# Small_e-PaperShield_v2_1.net
KiCad netlist of a schematic drawn in EAGLE
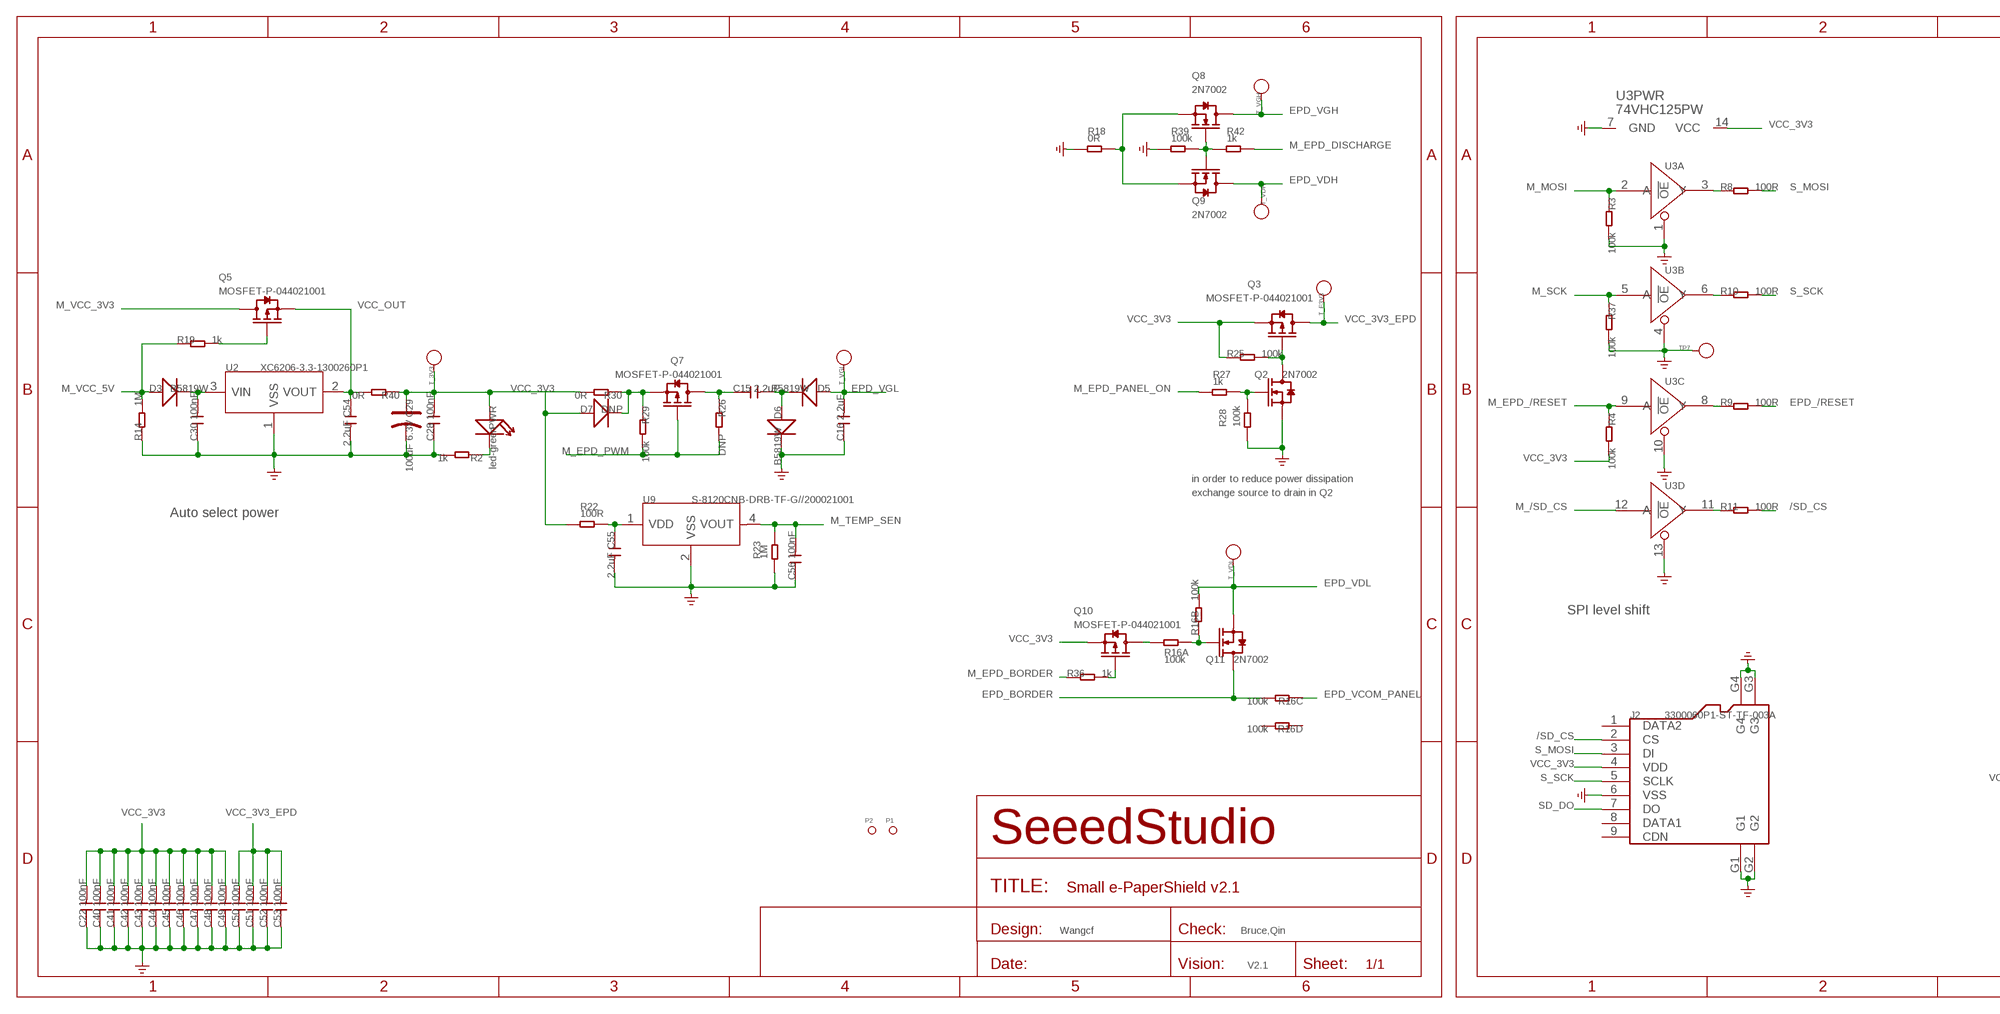
[diagram p0: schematic, sheet 1, part 1 of 2]
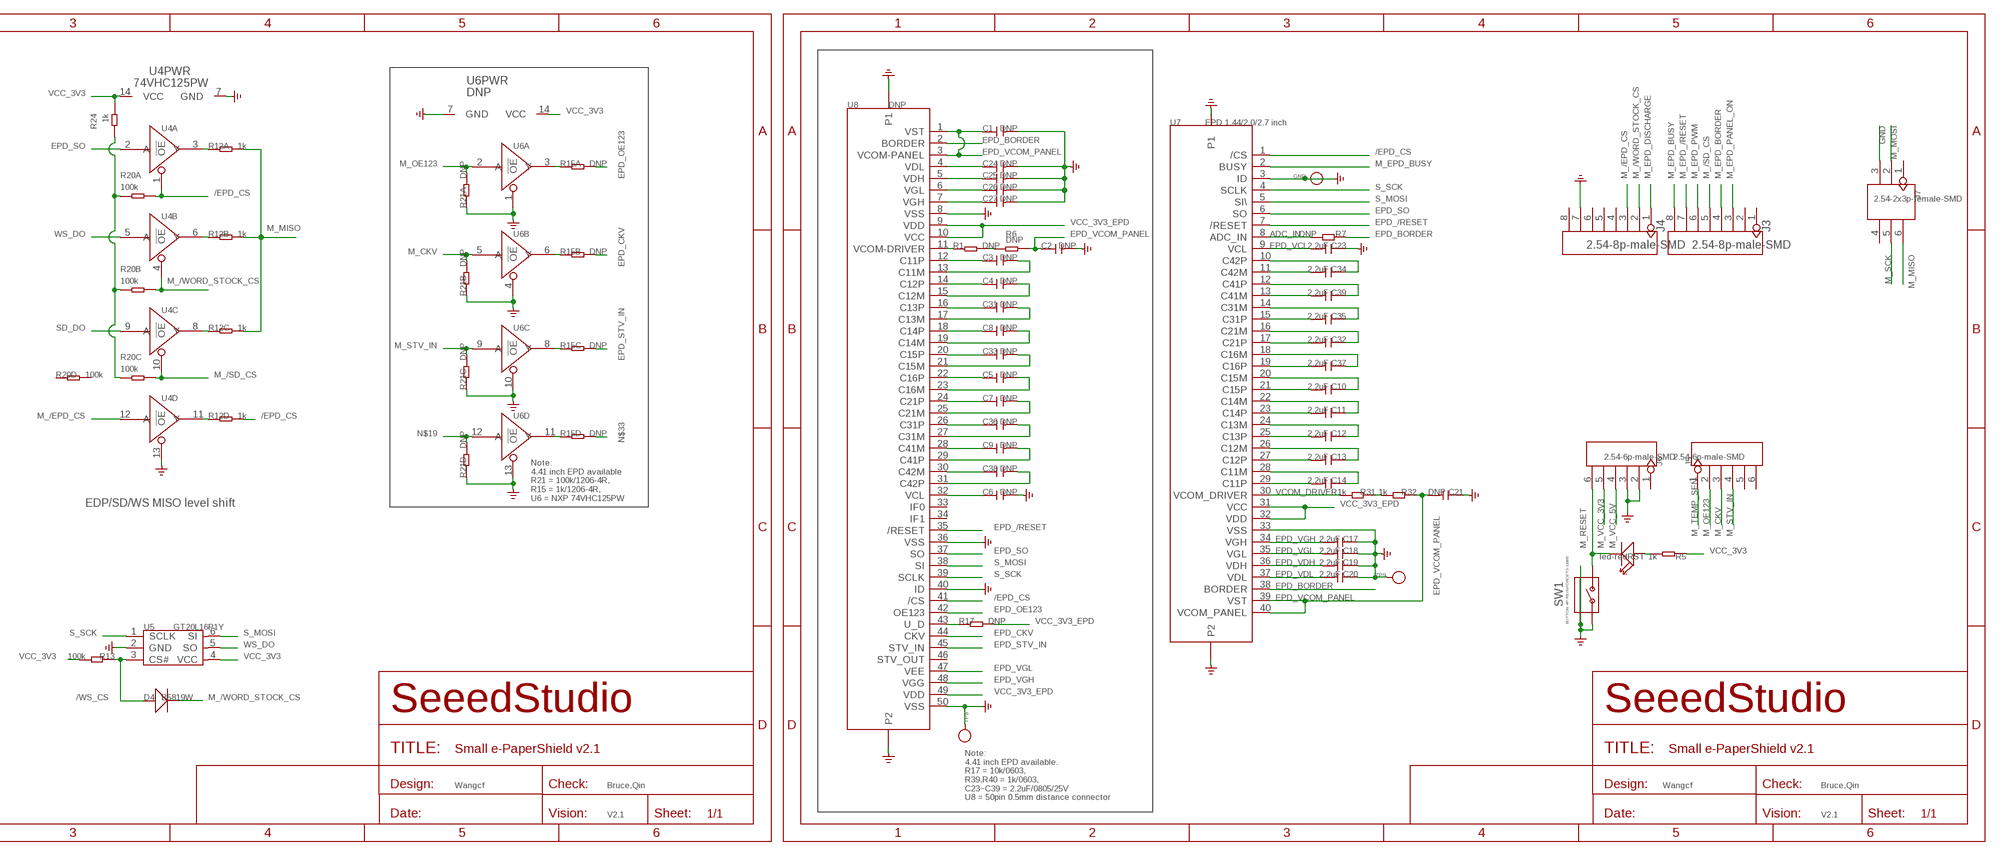
[diagram p1: schematic, sheet 1, part 2 of 2]

(export (version "E")
  (design (tool "Eeschema 10.0.6"))
  (components
    (comp (ref "C1")
      (value "DNP")
      (footprint "eagle-import:C0805")
      (libsource (lib "eagle-import") (part "C-0805"))
    )
    (comp (ref "C2")
      (value "DNP")
      (footprint "eagle-import:C0805")
      (libsource (lib "eagle-import") (part "C-0805"))
    )
    (comp (ref "C3")
      (value "DNP")
      (footprint "eagle-import:C0805")
      (libsource (lib "eagle-import") (part "C-0805"))
    )
    (comp (ref "C4")
      (value "DNP")
      (footprint "eagle-import:C0805")
      (libsource (lib "eagle-import") (part "C-0805"))
    )
    (comp (ref "C5")
      (value "DNP")
      (footprint "eagle-import:C0805")
      (libsource (lib "eagle-import") (part "C-0805"))
    )
    (comp (ref "C6")
      (value "DNP")
      (footprint "eagle-import:C0805")
      (libsource (lib "eagle-import") (part "C-0805"))
    )
    (comp (ref "C7")
      (value "DNP")
      (footprint "eagle-import:C0805")
      (libsource (lib "eagle-import") (part "C-0805"))
    )
    (comp (ref "C8")
      (value "DNP")
      (footprint "eagle-import:C0805")
      (libsource (lib "eagle-import") (part "C-0805"))
    )
    (comp (ref "C9")
      (value "DNP")
      (footprint "eagle-import:C0805")
      (libsource (lib "eagle-import") (part "C-0805"))
    )
    (comp (ref "C10")
      (value "2.2uF")
      (footprint "eagle-import:C0805")
      (libsource (lib "eagle-import") (part "C-0805"))
    )
    (comp (ref "C11")
      (value "2.2uF")
      (footprint "eagle-import:C0805")
      (libsource (lib "eagle-import") (part "C-0805"))
    )
    (comp (ref "C12")
      (value "2.2uF")
      (footprint "eagle-import:C0805")
      (libsource (lib "eagle-import") (part "C-0805"))
    )
    (comp (ref "C13")
      (value "2.2uF")
      (footprint "eagle-import:C0805")
      (libsource (lib "eagle-import") (part "C-0805"))
    )
    (comp (ref "C14")
      (value "2.2uF")
      (footprint "eagle-import:C0805")
      (libsource (lib "eagle-import") (part "C-0805"))
    )
    (comp (ref "C15")
      (value "2.2uF")
      (footprint "eagle-import:C0805")
      (libsource (lib "eagle-import") (part "C-0805"))
    )
    (comp (ref "C16")
      (value "2.2uF")
      (footprint "eagle-import:C0805")
      (libsource (lib "eagle-import") (part "C-0805"))
    )
    (comp (ref "C17")
      (value "2.2uF")
      (footprint "eagle-import:C0805")
      (libsource (lib "eagle-import") (part "C-0805"))
    )
    (comp (ref "C18")
      (value "2.2uF")
      (footprint "eagle-import:C0805")
      (libsource (lib "eagle-import") (part "C-0805"))
    )
    (comp (ref "C19")
      (value "2.2uF")
      (footprint "eagle-import:C0805")
      (libsource (lib "eagle-import") (part "C-0805"))
    )
    (comp (ref "C20")
      (value "2.2uF")
      (footprint "eagle-import:C0805")
      (libsource (lib "eagle-import") (part "C-0805"))
    )
    (comp (ref "C21")
      (value "DNP")
      (footprint "eagle-import:C0805")
      (libsource (lib "eagle-import") (part "C-0805"))
    )
    (comp (ref "C22")
      (value "100nF")
      (footprint "eagle-import:C0603")
      (libsource (lib "eagle-import") (part "C-0603"))
    )
    (comp (ref "C23")
      (value "2.2uF")
      (footprint "eagle-import:C0805")
      (libsource (lib "eagle-import") (part "C-0805"))
    )
    (comp (ref "C24")
      (value "DNP")
      (footprint "eagle-import:C0805")
      (libsource (lib "eagle-import") (part "C-0805"))
    )
    (comp (ref "C25")
      (value "DNP")
      (footprint "eagle-import:C0805")
      (libsource (lib "eagle-import") (part "C-0805"))
    )
    (comp (ref "C26")
      (value "DNP")
      (footprint "eagle-import:C0805")
      (libsource (lib "eagle-import") (part "C-0805"))
    )
    (comp (ref "C27")
      (value "DNP")
      (footprint "eagle-import:C0805")
      (libsource (lib "eagle-import") (part "C-0805"))
    )
    (comp (ref "C28")
      (value "100nF")
      (footprint "eagle-import:C0603")
      (libsource (lib "eagle-import") (part "C-0603"))
    )
    (comp (ref "C29")
      (value "100uF 6.3V")
      (footprint "eagle-import:AVX-B")
      (libsource (lib "eagle-import") (part "CAP-AVX-B"))
    )
    (comp (ref "C30")
      (value "100nF")
      (footprint "eagle-import:C0603")
      (libsource (lib "eagle-import") (part "C-0603"))
    )
    (comp (ref "C31")
      (value "DNP")
      (footprint "eagle-import:C0805")
      (libsource (lib "eagle-import") (part "C-0805"))
    )
    (comp (ref "C32")
      (value "2.2uF")
      (footprint "eagle-import:C0805")
      (libsource (lib "eagle-import") (part "C-0805"))
    )
    (comp (ref "C33")
      (value "DNP")
      (footprint "eagle-import:C0805")
      (libsource (lib "eagle-import") (part "C-0805"))
    )
    (comp (ref "C34")
      (value "2.2uF")
      (footprint "eagle-import:C0805")
      (libsource (lib "eagle-import") (part "C-0805"))
    )
    (comp (ref "C35")
      (value "2.2uF")
      (footprint "eagle-import:C0805")
      (libsource (lib "eagle-import") (part "C-0805"))
    )
    (comp (ref "C36")
      (value "DNP")
      (footprint "eagle-import:C0805")
      (libsource (lib "eagle-import") (part "C-0805"))
    )
    (comp (ref "C37")
      (value "2.2uF")
      (footprint "eagle-import:C0805")
      (libsource (lib "eagle-import") (part "C-0805"))
    )
    (comp (ref "C38")
      (value "DNP")
      (footprint "eagle-import:C0805")
      (libsource (lib "eagle-import") (part "C-0805"))
    )
    (comp (ref "C39")
      (value "2.2uF")
      (footprint "eagle-import:C0805")
      (libsource (lib "eagle-import") (part "C-0805"))
    )
    (comp (ref "C40")
      (value "100nF")
      (footprint "eagle-import:C0603")
      (libsource (lib "eagle-import") (part "C-0603"))
    )
    (comp (ref "C41")
      (value "100nF")
      (footprint "eagle-import:C0603")
      (libsource (lib "eagle-import") (part "C-0603"))
    )
    (comp (ref "C42")
      (value "100nF")
      (footprint "eagle-import:C0603")
      (libsource (lib "eagle-import") (part "C-0603"))
    )
    (comp (ref "C43")
      (value "100nF")
      (footprint "eagle-import:C0603")
      (libsource (lib "eagle-import") (part "C-0603"))
    )
    (comp (ref "C44")
      (value "100nF")
      (footprint "eagle-import:C0603")
      (libsource (lib "eagle-import") (part "C-0603"))
    )
    (comp (ref "C45")
      (value "100nF")
      (footprint "eagle-import:C0603")
      (libsource (lib "eagle-import") (part "C-0603"))
    )
    (comp (ref "C46")
      (value "100nF")
      (footprint "eagle-import:C0603")
      (libsource (lib "eagle-import") (part "C-0603"))
    )
    (comp (ref "C47")
      (value "100nF")
      (footprint "eagle-import:C0603")
      (libsource (lib "eagle-import") (part "C-0603"))
    )
    (comp (ref "C48")
      (value "100nF")
      (footprint "eagle-import:C0603")
      (libsource (lib "eagle-import") (part "C-0603"))
    )
    (comp (ref "C49")
      (value "100nF")
      (footprint "eagle-import:C0603")
      (libsource (lib "eagle-import") (part "C-0603"))
    )
    (comp (ref "C50")
      (value "100nF")
      (footprint "eagle-import:C0603")
      (libsource (lib "eagle-import") (part "C-0603"))
    )
    (comp (ref "C51")
      (value "100nF")
      (footprint "eagle-import:C0603")
      (libsource (lib "eagle-import") (part "C-0603"))
    )
    (comp (ref "C52")
      (value "100nF")
      (footprint "eagle-import:C0603")
      (libsource (lib "eagle-import") (part "C-0603"))
    )
    (comp (ref "C53")
      (value "100nF")
      (footprint "eagle-import:C0603")
      (libsource (lib "eagle-import") (part "C-0603"))
    )
    (comp (ref "C54")
      (value "2.2uF")
      (footprint "eagle-import:C0805")
      (libsource (lib "eagle-import") (part "C-0805"))
    )
    (comp (ref "C55")
      (value "2.2uF")
      (footprint "eagle-import:C0805")
      (libsource (lib "eagle-import") (part "C-0805"))
    )
    (comp (ref "C56")
      (value "100nF")
      (footprint "eagle-import:C0603")
      (libsource (lib "eagle-import") (part "C-0603"))
    )
    (comp (ref "D3")
      (value "B5819W")
      (footprint "eagle-import:SOD123")
      (libsource (lib "eagle-import") (part "D'1206'"))
    )
    (comp (ref "D4")
      (value "B5819W")
      (footprint "eagle-import:SOD123")
      (libsource (lib "eagle-import") (part "D'1206'"))
    )
    (comp (ref "D5")
      (value "B5819W")
      (footprint "eagle-import:SOD123")
      (libsource (lib "eagle-import") (part "D'1206'"))
    )
    (comp (ref "D6")
      (value "B5819W")
      (footprint "eagle-import:SOD123")
      (libsource (lib "eagle-import") (part "D'1206'"))
    )
    (comp (ref "D7")
      (value "DNP")
      (footprint "eagle-import:SOD123")
      (libsource (lib "eagle-import") (part "D'1206'"))
    )
    (comp (ref "GND")
      (value "PAD-TEST-POINT'3535'")
      (footprint "eagle-import:TP_3535")
      (fields (field (name "PARTNO") "DNP"))
      (libsource (lib "eagle-import") (part "PAD-TEST-POINT'3535'"))
    )
    (comp (ref "J2")
      (value "3300060P1-ST-TF-003A")
      (footprint "eagle-import:9P-SMD-W_-RING")
      (libsource (lib "eagle-import") (part "3300060P1-ST-TF-003A"))
    )
    (comp (ref "J3")
      (value "2.54-8p-male-SMD")
      (footprint "eagle-import:8P-2.54-SMD")
      (libsource (lib "eagle-import") (part "HEADER-8P-2.54-SMD"))
    )
    (comp (ref "J4")
      (value "2.54-8p-male-SMD")
      (footprint "eagle-import:8P-2.54-SMD")
      (libsource (lib "eagle-import") (part "HEADER-8P-2.54-SMD"))
    )
    (comp (ref "J5")
      (value "2.54-6p-male-SMD")
      (footprint "eagle-import:6P-2.54-SMD")
      (libsource (lib "eagle-import") (part "HEADER-6P-SMD"))
    )
    (comp (ref "J6")
      (value "2.54-6p-male-SMD")
      (footprint "eagle-import:6P-2.54-SMD")
      (libsource (lib "eagle-import") (part "HEADER-6P-SMD"))
    )
    (comp (ref "J7")
      (value "2.54-2x3p-female-SMD")
      (footprint "eagle-import:2X3P-2.54-SMD")
      (libsource (lib "eagle-import") (part "HEADER-2X3P-SMD"))
    )
    (comp (ref "P1")
      (value "PAD-MARK")
      (footprint "eagle-import:ROUND-MARK-1.0")
      (fields (field (name "PARTNO") "DNP"))
      (libsource (lib "eagle-import") (part "PAD-MARK"))
    )
    (comp (ref "P2")
      (value "PAD-MARK")
      (footprint "eagle-import:ROUND-MARK-1.0")
      (fields (field (name "PARTNO") "DNP"))
      (libsource (lib "eagle-import") (part "PAD-MARK"))
    )
    (comp (ref "PWR")
      (value "led-green")
      (footprint "eagle-import:LED-SIDE-VIEW-0603-RIGHT")
      (libsource (lib "eagle-import") (part "LED'RIGHT'"))
    )
    (comp (ref "Q2")
      (value "2N7002")
      (footprint "eagle-import:SOT23")
      (libsource (lib "eagle-import") (part "MOSFET-N'SOT23'"))
    )
    (comp (ref "Q3")
      (value "MOSFET-P-044021001")
      (footprint "eagle-import:SOT23")
      (libsource (lib "eagle-import") (part "MOSFET-P-044021001"))
    )
    (comp (ref "Q5")
      (value "MOSFET-P-044021001")
      (footprint "eagle-import:SOT23")
      (libsource (lib "eagle-import") (part "MOSFET-P-044021001"))
    )
    (comp (ref "Q7")
      (value "MOSFET-P-044021001")
      (footprint "eagle-import:SOT23")
      (libsource (lib "eagle-import") (part "MOSFET-P-044021001"))
    )
    (comp (ref "Q8")
      (value "2N7002")
      (footprint "eagle-import:SOT23")
      (libsource (lib "eagle-import") (part "MOSFET-N'SOT23'"))
    )
    (comp (ref "Q9")
      (value "2N7002")
      (footprint "eagle-import:SOT23")
      (libsource (lib "eagle-import") (part "MOSFET-N'SOT23'"))
    )
    (comp (ref "Q10")
      (value "MOSFET-P-044021001")
      (footprint "eagle-import:SOT23")
      (libsource (lib "eagle-import") (part "MOSFET-P-044021001"))
    )
    (comp (ref "Q11")
      (value "2N7002")
      (footprint "eagle-import:SOT23")
      (libsource (lib "eagle-import") (part "MOSFET-N'SOT23'"))
    )
    (comp (ref "R1")
      (value "DNP")
      (footprint "eagle-import:R0603")
      (libsource (lib "eagle-import") (part "R-0603"))
    )
    (comp (ref "R2")
      (value "1k")
      (footprint "eagle-import:R0603")
      (libsource (lib "eagle-import") (part "R-0603"))
    )
    (comp (ref "R3")
      (value "100k")
      (footprint "eagle-import:R0603")
      (libsource (lib "eagle-import") (part "R-0603"))
    )
    (comp (ref "R4")
      (value "100k")
      (footprint "eagle-import:R0603")
      (libsource (lib "eagle-import") (part "R-0603"))
    )
    (comp (ref "R5")
      (value "1k")
      (footprint "eagle-import:R0603")
      (libsource (lib "eagle-import") (part "R-0603"))
    )
    (comp (ref "R6")
      (value "DNP")
      (footprint "eagle-import:R0603")
      (libsource (lib "eagle-import") (part "R-0603"))
    )
    (comp (ref "R7")
      (value "DNP")
      (footprint "eagle-import:R0603")
      (libsource (lib "eagle-import") (part "R-0603"))
    )
    (comp (ref "R8")
      (value "100R")
      (footprint "eagle-import:R0603")
      (libsource (lib "eagle-import") (part "R-0603"))
    )
    (comp (ref "R9")
      (value "100R")
      (footprint "eagle-import:R0603")
      (libsource (lib "eagle-import") (part "R-0603"))
    )
    (comp (ref "R10")
      (value "100R")
      (footprint "eagle-import:R0603")
      (libsource (lib "eagle-import") (part "R-0603"))
    )
    (comp (ref "R11")
      (value "100R")
      (footprint "eagle-import:R0603")
      (libsource (lib "eagle-import") (part "R-0603"))
    )
    (comp (ref "R12")
      (value "1k")
      (footprint "eagle-import:1206-8-3.3X2.4")
      (libsource (lib "eagle-import") (part "R-4R-1206"))
    )
    (comp (ref "R13")
      (value "100k")
      (footprint "eagle-import:R0603")
      (libsource (lib "eagle-import") (part "R-0603"))
    )
    (comp (ref "R14")
      (value "1M")
      (footprint "eagle-import:R0603")
      (libsource (lib "eagle-import") (part "R-0603"))
    )
    (comp (ref "R15")
      (value "DNP")
      (footprint "eagle-import:1206-8-3.3X2.4")
      (libsource (lib "eagle-import") (part "R-4R-1206"))
    )
    (comp (ref "R16")
      (value "100k")
      (footprint "eagle-import:1206-8-3.3X2.4")
      (libsource (lib "eagle-import") (part "R-4R-1206"))
    )
    (comp (ref "R17")
      (value "DNP")
      (footprint "eagle-import:R0603")
      (libsource (lib "eagle-import") (part "R-0603"))
    )
    (comp (ref "R18")
      (value "0R")
      (footprint "eagle-import:R0603")
      (libsource (lib "eagle-import") (part "R-0603"))
    )
    (comp (ref "R19")
      (value "1k")
      (footprint "eagle-import:R0603")
      (libsource (lib "eagle-import") (part "R-0603"))
    )
    (comp (ref "R20")
      (value "100k")
      (footprint "eagle-import:1206-8-3.3X2.4")
      (libsource (lib "eagle-import") (part "R-4R-1206"))
    )
    (comp (ref "R21")
      (value "DNP")
      (footprint "eagle-import:1206-8-3.3X2.4")
      (libsource (lib "eagle-import") (part "R-4R-1206"))
    )
    (comp (ref "R22")
      (value "100R")
      (footprint "eagle-import:R0603")
      (libsource (lib "eagle-import") (part "R-0603"))
    )
    (comp (ref "R23")
      (value "1M")
      (footprint "eagle-import:R0603")
      (libsource (lib "eagle-import") (part "R-0603"))
    )
    (comp (ref "R24")
      (value "1k")
      (footprint "eagle-import:R0603")
      (libsource (lib "eagle-import") (part "R-0603"))
    )
    (comp (ref "R25")
      (value "100k")
      (footprint "eagle-import:R0603")
      (libsource (lib "eagle-import") (part "R-0603"))
    )
    (comp (ref "R26")
      (value "DNP")
      (footprint "eagle-import:R0603")
      (libsource (lib "eagle-import") (part "R-0603"))
    )
    (comp (ref "R27")
      (value "1k")
      (footprint "eagle-import:R0603")
      (libsource (lib "eagle-import") (part "R-0603"))
    )
    (comp (ref "R28")
      (value "100k")
      (footprint "eagle-import:R0603")
      (libsource (lib "eagle-import") (part "R-0603"))
    )
    (comp (ref "R29")
      (value "100k")
      (footprint "eagle-import:R0603")
      (libsource (lib "eagle-import") (part "R-0603"))
    )
    (comp (ref "R30")
      (value "0R")
      (footprint "eagle-import:R0603")
      (libsource (lib "eagle-import") (part "R-0603"))
    )
    (comp (ref "R31")
      (value "1k")
      (footprint "eagle-import:R0603")
      (libsource (lib "eagle-import") (part "R-0603"))
    )
    (comp (ref "R32")
      (value "1k")
      (footprint "eagle-import:R0603")
      (libsource (lib "eagle-import") (part "R-0603"))
    )
    (comp (ref "R36")
      (value "1k")
      (footprint "eagle-import:R0603")
      (libsource (lib "eagle-import") (part "R-0603"))
    )
    (comp (ref "R37")
      (value "100k")
      (footprint "eagle-import:R0603")
      (libsource (lib "eagle-import") (part "R-0603"))
    )
    (comp (ref "R39")
      (value "100k")
      (footprint "eagle-import:R0603")
      (libsource (lib "eagle-import") (part "R-0603"))
    )
    (comp (ref "R40")
      (value "0R")
      (footprint "eagle-import:R0603")
      (libsource (lib "eagle-import") (part "R-0603"))
    )
    (comp (ref "R42")
      (value "1k")
      (footprint "eagle-import:R0603")
      (libsource (lib "eagle-import") (part "R-0603"))
    )
    (comp (ref "RST")
      (value "led-red")
      (footprint "eagle-import:LED-SIDE-VIEW-0603-RIGHT")
      (libsource (lib "eagle-import") (part "LED'RIGHT'"))
    )
    (comp (ref "SW1")
      (value "BUTTON-4P-REINFORCE'TS-1188E'")
      (footprint "eagle-import:4P-SMD-7X3.5X3.5H")
      (libsource (lib "eagle-import") (part "BUTTON-4P-REINFORCE'TS-1188E'"))
    )
    (comp (ref "TP7")
      (value "PAD-TEST-POINT'3535'")
      (footprint "eagle-import:TP_3535")
      (fields (field (name "PARTNO") "DNP"))
      (libsource (lib "eagle-import") (part "PAD-TEST-POINT'3535'"))
    )
    (comp (ref "TP8")
      (value "PAD-TEST-POINT'3535'")
      (footprint "eagle-import:TP_3535")
      (fields (field (name "PARTNO") "DNP"))
      (libsource (lib "eagle-import") (part "PAD-TEST-POINT'3535'"))
    )
    (comp (ref "TP9")
      (value "PAD-TEST-POINT'3535'")
      (footprint "eagle-import:TP_3535")
      (fields (field (name "PARTNO") "DNP"))
      (libsource (lib "eagle-import") (part "PAD-TEST-POINT'3535'"))
    )
    (comp (ref "T_3V3")
      (value "PAD-TEST-POINT'3535'")
      (footprint "eagle-import:TP_3535")
      (fields (field (name "PARTNO") "DNP"))
      (libsource (lib "eagle-import") (part "PAD-TEST-POINT'3535'"))
    )
    (comp (ref "T_E3V3")
      (value "PAD-TEST-POINT'3535'")
      (footprint "eagle-import:TP_3535")
      (fields (field (name "PARTNO") "DNP"))
      (libsource (lib "eagle-import") (part "PAD-TEST-POINT'3535'"))
    )
    (comp (ref "T_VDH")
      (value "PAD-TEST-POINT'3535'")
      (footprint "eagle-import:TP_3535")
      (fields (field (name "PARTNO") "DNP"))
      (libsource (lib "eagle-import") (part "PAD-TEST-POINT'3535'"))
    )
    (comp (ref "T_VDL")
      (value "PAD-TEST-POINT'3535'")
      (footprint "eagle-import:TP_3535")
      (fields (field (name "PARTNO") "DNP"))
      (libsource (lib "eagle-import") (part "PAD-TEST-POINT'3535'"))
    )
    (comp (ref "T_VGH")
      (value "PAD-TEST-POINT'3535'")
      (footprint "eagle-import:TP_3535")
      (fields (field (name "PARTNO") "DNP"))
      (libsource (lib "eagle-import") (part "PAD-TEST-POINT'3535'"))
    )
    (comp (ref "T_VGL")
      (value "PAD-TEST-POINT'3535'")
      (footprint "eagle-import:TP_3535")
      (fields (field (name "PARTNO") "DNP"))
      (libsource (lib "eagle-import") (part "PAD-TEST-POINT'3535'"))
    )
    (comp (ref "U2")
      (value "XC6206-3.3-1300260P1")
      (footprint "eagle-import:SOT23")
      (libsource (lib "eagle-import") (part "XC6206-3.3-1300260P1"))
    )
    (comp (ref "U3")
      (value "74VHC125PW")
      (footprint "eagle-import:TSSOP14")
      (libsource (lib "eagle-import") (part "74V125PWHC"))
    )
    (comp (ref "U4")
      (value "74VHC125PW")
      (footprint "eagle-import:TSSOP14")
      (libsource (lib "eagle-import") (part "74V125PWHC"))
    )
    (comp (ref "U5")
      (value "GT20L16P1Y")
      (footprint "eagle-import:SOT23-6")
      (libsource (lib "eagle-import") (part "GT20L16P1Y"))
    )
    (comp (ref "U6")
      (value "DNP")
      (footprint "eagle-import:TSSOP14")
      (libsource (lib "eagle-import") (part "74V125PWHC"))
    )
    (comp (ref "U7")
      (value "EPD 1.44/2.0/2.7 inch")
      (footprint "eagle-import:40P-0.5")
      (libsource (lib "eagle-import") (part "TFT-EPD-PANEL"))
    )
    (comp (ref "U8")
      (value "DNP")
      (footprint "eagle-import:50P-0.5")
      (libsource (lib "eagle-import") (part "template_TFT-EPD-PANEL"))
    )
    (comp (ref "U9")
      (value "S-8120CNB-DRB-TF-G//200021001")
      (footprint "eagle-import:SC-82AB")
      (libsource (lib "eagle-import") (part "S-8110C/8120C"))
    )
  )
  (nets
    (net (code "1") (name "/ADC_IN") (class "Default")
      (node (ref "R7") (pin "2") (pinfunction "2_2") (pintype "passive"))
      (node (ref "U7") (pin "8") (pinfunction "ADC_IN_8") (pintype "bidirectional"))
    )
    (net (code "2") (name "/EPD_BORDER") (class "Default")
      (node (ref "Q11") (pin "3") (pinfunction "D_3") (pintype "passive"))
      (node (ref "R16") (pin "6") (pinfunction "2_6") (pintype "passive"))
      (node (ref "R7") (pin "1") (pinfunction "1_1") (pintype "passive"))
      (node (ref "U7") (pin "38") (pinfunction "BORDER_38") (pintype "bidirectional"))
      (node (ref "U8") (pin "2") (pinfunction "BORDER_2") (pintype "bidirectional"))
    )
    (net (code "3") (name "/EPD_CKV") (class "Default")
      (node (ref "R15") (pin "7") (pinfunction "2_7") (pintype "passive"))
      (node (ref "U8") (pin "44") (pinfunction "CKV_44") (pintype "bidirectional"))
    )
    (net (code "4") (name "/EPD_OE123") (class "Default")
      (node (ref "R15") (pin "8") (pinfunction "2_8") (pintype "passive"))
      (node (ref "U8") (pin "42") (pinfunction "OE123_42") (pintype "bidirectional"))
    )
    (net (code "5") (name "/EPD_SO") (class "Default")
      (node (ref "U4") (pin "2") (pinfunction "A_2") (pintype "bidirectional"))
      (node (ref "U7") (pin "6") (pinfunction "SO_6") (pintype "bidirectional"))
      (node (ref "U8") (pin "37") (pinfunction "SO_37") (pintype "bidirectional"))
    )
    (net (code "6") (name "/EPD_STV_IN") (class "Default")
      (node (ref "R15") (pin "6") (pinfunction "2_6") (pintype "passive"))
      (node (ref "U8") (pin "45") (pinfunction "STV_IN_45") (pintype "bidirectional"))
    )
    (net (code "7") (name "/EPD_VCL") (class "Default")
      (node (ref "C23") (pin "2") (pinfunction "2_2") (pintype "passive"))
      (node (ref "U7") (pin "9") (pinfunction "VCL_9") (pintype "bidirectional"))
    )
    (net (code "8") (name "/EPD_VCOM_PANEL") (class "Default")
      (node (ref "C1") (pin "1") (pinfunction "1_1") (pintype "passive"))
      (node (ref "C2") (pin "1") (pinfunction "1_1") (pintype "passive"))
      (node (ref "C21") (pin "2") (pinfunction "2_2") (pintype "passive"))
      (node (ref "R16") (pin "3") (pinfunction "1_3") (pintype "passive"))
      (node (ref "R32") (pin "1") (pinfunction "1_1") (pintype "passive"))
      (node (ref "R6") (pin "2") (pinfunction "2_2") (pintype "passive"))
      (node (ref "U7") (pin "39") (pinfunction "VST_39") (pintype "bidirectional"))
      (node (ref "U7") (pin "40") (pinfunction "VCOM_PANEL_40") (pintype "bidirectional"))
      (node (ref "U8") (pin "1") (pinfunction "VST_1") (pintype "bidirectional"))
      (node (ref "U8") (pin "3") (pinfunction "VCOM-PANEL_3") (pintype "bidirectional"))
    )
    (net (code "9") (name "/EPD_VDH") (class "Default")
      (node (ref "C19") (pin "2") (pinfunction "2_2") (pintype "passive"))
      (node (ref "C25") (pin "1") (pinfunction "1_1") (pintype "passive"))
      (node (ref "Q9") (pin "3") (pinfunction "D_3") (pintype "passive"))
      (node (ref "T_VDH") (pin "T") (pinfunction "T_T") (pintype "bidirectional"))
      (node (ref "U7") (pin "36") (pinfunction "VDH_36") (pintype "bidirectional"))
      (node (ref "U8") (pin "5") (pinfunction "VDH_5") (pintype "bidirectional"))
    )
    (net (code "10") (name "/EPD_VDL") (class "Default")
      (node (ref "C20") (pin "2") (pinfunction "2_2") (pintype "passive"))
      (node (ref "C24") (pin "1") (pinfunction "1_1") (pintype "passive"))
      (node (ref "Q11") (pin "2") (pinfunction "S_2") (pintype "passive"))
      (node (ref "R16") (pin "7") (pinfunction "2_7") (pintype "passive"))
      (node (ref "T_VDL") (pin "T") (pinfunction "T_T") (pintype "bidirectional"))
      (node (ref "U7") (pin "37") (pinfunction "VDL_37") (pintype "bidirectional"))
      (node (ref "U8") (pin "4") (pinfunction "VDL_4") (pintype "bidirectional"))
    )
    (net (code "11") (name "/EPD_VGH") (class "Default")
      (node (ref "C17") (pin "2") (pinfunction "2_2") (pintype "passive"))
      (node (ref "C27") (pin "1") (pinfunction "1_1") (pintype "passive"))
      (node (ref "Q8") (pin "3") (pinfunction "D_3") (pintype "passive"))
      (node (ref "T_VGH") (pin "T") (pinfunction "T_T") (pintype "bidirectional"))
      (node (ref "U7") (pin "34") (pinfunction "VGH_34") (pintype "bidirectional"))
      (node (ref "U8") (pin "48") (pinfunction "VGG_48") (pintype "bidirectional"))
      (node (ref "U8") (pin "7") (pinfunction "VGH_7") (pintype "bidirectional"))
    )
    (net (code "12") (name "/EPD_VGL") (class "Default")
      (node (ref "C16") (pin "2") (pinfunction "2_2") (pintype "passive"))
      (node (ref "C18") (pin "2") (pinfunction "2_2") (pintype "passive"))
      (node (ref "C26") (pin "1") (pinfunction "1_1") (pintype "passive"))
      (node (ref "D5") (pin "+") (pinfunction "+_+") (pintype "passive"))
      (node (ref "T_VGL") (pin "T") (pinfunction "T_T") (pintype "bidirectional"))
      (node (ref "U7") (pin "35") (pinfunction "VGL_35") (pintype "bidirectional"))
      (node (ref "U8") (pin "47") (pinfunction "VEE_47") (pintype "bidirectional"))
      (node (ref "U8") (pin "6") (pinfunction "VGL_6") (pintype "bidirectional"))
    )
    (net (code "13") (name "/EPD_{slash}RESET") (class "Default")
      (node (ref "R9") (pin "2") (pinfunction "2_2") (pintype "passive"))
      (node (ref "U7") (pin "7") (pinfunction "/RESET_7") (pintype "bidirectional"))
      (node (ref "U8") (pin "35") (pinfunction "/RESET_35") (pintype "bidirectional"))
    )
    (net (code "14") (name "/M_CKV") (class "Default")
      (node (ref "J5") (pin "3") (pinfunction "3_3") (pintype "bidirectional"))
      (node (ref "R21") (pin "7") (pinfunction "2_7") (pintype "passive"))
      (node (ref "U6") (pin "5") (pinfunction "A_5") (pintype "bidirectional"))
    )
    (net (code "15") (name "/M_EPD_BORDER") (class "Default")
      (node (ref "J3") (pin "4") (pinfunction "4_4") (pintype "bidirectional"))
      (node (ref "R36") (pin "1") (pinfunction "1_1") (pintype "passive"))
    )
    (net (code "16") (name "/M_EPD_BUSY") (class "Default")
      (node (ref "J3") (pin "8") (pinfunction "8_8") (pintype "bidirectional"))
      (node (ref "U7") (pin "2") (pinfunction "BUSY_2") (pintype "bidirectional"))
    )
    (net (code "17") (name "/M_EPD_DISCHARGE") (class "Default")
      (node (ref "J4") (pin "1") (pinfunction "1_1") (pintype "bidirectional"))
      (node (ref "R42") (pin "2") (pinfunction "2_2") (pintype "passive"))
    )
    (net (code "18") (name "/M_EPD_PANEL_ON") (class "Default")
      (node (ref "J3") (pin "3") (pinfunction "3_3") (pintype "bidirectional"))
      (node (ref "R27") (pin "1") (pinfunction "1_1") (pintype "passive"))
    )
    (net (code "19") (name "/M_EPD_PWM") (class "Default")
      (node (ref "J3") (pin "6") (pinfunction "6_6") (pintype "bidirectional"))
      (node (ref "Q7") (pin "1") (pinfunction "G_1") (pintype "passive"))
      (node (ref "R26") (pin "2") (pinfunction "2_2") (pintype "passive"))
      (node (ref "R29") (pin "2") (pinfunction "2_2") (pintype "passive"))
    )
    (net (code "20") (name "/M_EPD_{slash}RESET") (class "Default")
      (node (ref "J3") (pin "7") (pinfunction "7_7") (pintype "bidirectional"))
      (node (ref "R4") (pin "1") (pinfunction "1_1") (pintype "passive"))
      (node (ref "U3") (pin "9") (pinfunction "A_9") (pintype "bidirectional"))
    )
    (net (code "21") (name "/M_MISO") (class "Default")
      (node (ref "J7") (pin "6") (pinfunction "6_6") (pintype "bidirectional"))
      (node (ref "R12") (pin "6") (pinfunction "2_6") (pintype "passive"))
      (node (ref "R12") (pin "7") (pinfunction "2_7") (pintype "passive"))
      (node (ref "R12") (pin "8") (pinfunction "2_8") (pintype "passive"))
    )
    (net (code "22") (name "/M_MOSI") (class "Default")
      (node (ref "J7") (pin "2") (pinfunction "2_2") (pintype "bidirectional"))
      (node (ref "R3") (pin "1") (pinfunction "1_1") (pintype "passive"))
      (node (ref "U3") (pin "2") (pinfunction "A_2") (pintype "bidirectional"))
    )
    (net (code "23") (name "/M_OE123") (class "Default")
      (node (ref "J5") (pin "2") (pinfunction "2_2") (pintype "bidirectional"))
      (node (ref "R21") (pin "8") (pinfunction "2_8") (pintype "passive"))
      (node (ref "U6") (pin "2") (pinfunction "A_2") (pintype "bidirectional"))
    )
    (net (code "24") (name "/M_RESET") (class "Default")
      (node (ref "J6") (pin "6") (pinfunction "6_6") (pintype "bidirectional"))
      (node (ref "RST") (pin "2") (pinfunction "-_2") (pintype "passive"))
      (node (ref "SW1") (pin "2") (pinfunction "2_2") (pintype "bidirectional"))
    )
    (net (code "25") (name "/M_SCK") (class "Default")
      (node (ref "J7") (pin "5") (pinfunction "5_5") (pintype "bidirectional"))
      (node (ref "R37") (pin "1") (pinfunction "1_1") (pintype "passive"))
      (node (ref "U3") (pin "5") (pinfunction "A_5") (pintype "bidirectional"))
    )
    (net (code "26") (name "/M_STV_IN") (class "Default")
      (node (ref "J5") (pin "4") (pinfunction "4_4") (pintype "bidirectional"))
      (node (ref "R21") (pin "6") (pinfunction "2_6") (pintype "passive"))
      (node (ref "U6") (pin "9") (pinfunction "A_9") (pintype "bidirectional"))
    )
    (net (code "27") (name "/M_TEMP_SEN") (class "Default")
      (node (ref "C56") (pin "2") (pinfunction "2_2") (pintype "passive"))
      (node (ref "J5") (pin "1") (pinfunction "1_1") (pintype "bidirectional"))
      (node (ref "R23") (pin "2") (pinfunction "2_2") (pintype "passive"))
      (node (ref "U9") (pin "4") (pinfunction "VOUT_4") (pintype "output"))
    )
    (net (code "28") (name "/M_VCC_3V3") (class "Default")
      (node (ref "J6") (pin "5") (pinfunction "5_5") (pintype "bidirectional"))
      (node (ref "Q5") (pin "3") (pinfunction "D_3") (pintype "passive"))
    )
    (net (code "29") (name "/M_VCC_5V") (class "Default")
      (node (ref "D3") (pin "+") (pinfunction "+_+") (pintype "passive"))
      (node (ref "J6") (pin "4") (pinfunction "4_4") (pintype "bidirectional"))
      (node (ref "R14") (pin "2") (pinfunction "2_2") (pintype "passive"))
      (node (ref "R19") (pin "1") (pinfunction "1_1") (pintype "passive"))
    )
    (net (code "30") (name "/M_{slash}EPD_CS") (class "Default")
      (node (ref "J4") (pin "3") (pinfunction "3_3") (pintype "bidirectional"))
      (node (ref "U4") (pin "12") (pinfunction "A_12") (pintype "bidirectional"))
    )
    (net (code "31") (name "/M_{slash}SD_CS") (class "Default")
      (node (ref "J3") (pin "5") (pinfunction "5_5") (pintype "bidirectional"))
      (node (ref "R20") (pin "6") (pinfunction "2_6") (pintype "passive"))
      (node (ref "U3") (pin "12") (pinfunction "A_12") (pintype "bidirectional"))
      (node (ref "U4") (pin "10") (pinfunction "~{OE}_10") (pintype "bidirectional"))
    )
    (net (code "32") (name "/M_{slash}WORD_STOCK_CS") (class "Default")
      (node (ref "D4") (pin "-") (pinfunction "-_-") (pintype "passive"))
      (node (ref "J4") (pin "2") (pinfunction "2_2") (pintype "bidirectional"))
      (node (ref "R20") (pin "7") (pinfunction "2_7") (pintype "passive"))
      (node (ref "U4") (pin "4") (pinfunction "~{OE}_4") (pintype "bidirectional"))
    )
    (net (code "33") (name "/N$19") (class "Default")
      (node (ref "R21") (pin "5") (pinfunction "2_5") (pintype "passive"))
      (node (ref "U6") (pin "12") (pinfunction "A_12") (pintype "bidirectional"))
    )
    (net (code "34") (name "/N$33") (class "Default")
      (node (ref "R15") (pin "5") (pinfunction "2_5") (pintype "passive"))
    )
    (net (code "35") (name "/SD_DO") (class "Default")
      (node (ref "J2") (pin "7") (pinfunction "DO_7") (pintype "bidirectional"))
      (node (ref "U4") (pin "9") (pinfunction "A_9") (pintype "bidirectional"))
    )
    (net (code "36") (name "/S_MOSI") (class "Default")
      (node (ref "J2") (pin "3") (pinfunction "DI_3") (pintype "bidirectional"))
      (node (ref "R8") (pin "2") (pinfunction "2_2") (pintype "passive"))
      (node (ref "U5") (pin "6") (pinfunction "SI_6") (pintype "input"))
      (node (ref "U7") (pin "5") (pinfunction "SI\\_5") (pintype "bidirectional"))
      (node (ref "U8") (pin "38") (pinfunction "SI_38") (pintype "bidirectional"))
    )
    (net (code "37") (name "/S_SCK") (class "Default")
      (node (ref "J2") (pin "5") (pinfunction "SCLK_5") (pintype "bidirectional"))
      (node (ref "R10") (pin "2") (pinfunction "2_2") (pintype "passive"))
      (node (ref "U5") (pin "1") (pinfunction "SCLK_1") (pintype "input"))
      (node (ref "U7") (pin "4") (pinfunction "SCLK_4") (pintype "bidirectional"))
      (node (ref "U8") (pin "39") (pinfunction "SCLK_39") (pintype "bidirectional"))
    )
    (net (code "38") (name "/VCC_3V3") (class "Default")
      (node (ref "C22") (pin "2") (pinfunction "2_2") (pintype "passive"))
      (node (ref "C28") (pin "2") (pinfunction "2_2") (pintype "passive"))
      (node (ref "C29") (pin "+") (pinfunction "+_+") (pintype "passive"))
      (node (ref "C40") (pin "2") (pinfunction "2_2") (pintype "passive"))
      (node (ref "C41") (pin "2") (pinfunction "2_2") (pintype "passive"))
      (node (ref "C42") (pin "2") (pinfunction "2_2") (pintype "passive"))
      (node (ref "C43") (pin "2") (pinfunction "2_2") (pintype "passive"))
      (node (ref "C44") (pin "2") (pinfunction "2_2") (pintype "passive"))
      (node (ref "C45") (pin "2") (pinfunction "2_2") (pintype "passive"))
      (node (ref "C46") (pin "2") (pinfunction "2_2") (pintype "passive"))
      (node (ref "C47") (pin "2") (pinfunction "2_2") (pintype "passive"))
      (node (ref "C48") (pin "2") (pinfunction "2_2") (pintype "passive"))
      (node (ref "C49") (pin "2") (pinfunction "2_2") (pintype "passive"))
      (node (ref "D7") (pin "+") (pinfunction "+_+") (pintype "passive"))
      (node (ref "J2") (pin "4") (pinfunction "VDD_4") (pintype "bidirectional"))
      (node (ref "PWR") (pin "1") (pinfunction "+_1") (pintype "passive"))
      (node (ref "Q10") (pin "2") (pinfunction "S_2") (pintype "passive"))
      (node (ref "Q3") (pin "2") (pinfunction "S_2") (pintype "passive"))
      (node (ref "R13") (pin "2") (pinfunction "2_2") (pintype "passive"))
      (node (ref "R22") (pin "1") (pinfunction "1_1") (pintype "passive"))
      (node (ref "R24") (pin "1") (pinfunction "1_1") (pintype "passive"))
      (node (ref "R25") (pin "1") (pinfunction "1_1") (pintype "passive"))
      (node (ref "R30") (pin "2") (pinfunction "2_2") (pintype "passive"))
      (node (ref "R4") (pin "2") (pinfunction "2_2") (pintype "passive"))
      (node (ref "R40") (pin "1") (pinfunction "1_1") (pintype "passive"))
      (node (ref "R5") (pin "1") (pinfunction "1_1") (pintype "passive"))
      (node (ref "T_3V3") (pin "T") (pinfunction "T_T") (pintype "bidirectional"))
      (node (ref "U3") (pin "14") (pinfunction "VCC_14") (pintype "power_in"))
      (node (ref "U4") (pin "14") (pinfunction "VCC_14") (pintype "power_in"))
      (node (ref "U5") (pin "4") (pinfunction "VCC_4") (pintype "power_in"))
      (node (ref "U6") (pin "14") (pinfunction "VCC_14") (pintype "power_in"))
    )
    (net (code "39") (name "/VCC_3V3_EPD") (class "Default")
      (node (ref "C50") (pin "2") (pinfunction "2_2") (pintype "passive"))
      (node (ref "C51") (pin "2") (pinfunction "2_2") (pintype "passive"))
      (node (ref "C52") (pin "2") (pinfunction "2_2") (pintype "passive"))
      (node (ref "C53") (pin "2") (pinfunction "2_2") (pintype "passive"))
      (node (ref "Q3") (pin "3") (pinfunction "D_3") (pintype "passive"))
      (node (ref "R17") (pin "2") (pinfunction "2_2") (pintype "passive"))
      (node (ref "T_E3V3") (pin "T") (pinfunction "T_T") (pintype "bidirectional"))
      (node (ref "U7") (pin "31") (pinfunction "VCC_31") (pintype "bidirectional"))
      (node (ref "U7") (pin "32") (pinfunction "VDD_32") (pintype "bidirectional"))
      (node (ref "U8") (pin "10") (pinfunction "VCC_10") (pintype "bidirectional"))
      (node (ref "U8") (pin "49") (pinfunction "VDD_49") (pintype "bidirectional"))
      (node (ref "U8") (pin "9") (pinfunction "VDD_9") (pintype "bidirectional"))
    )
    (net (code "40") (name "/VCC_OUT") (class "Default")
      (node (ref "C54") (pin "1") (pinfunction "1_1") (pintype "passive"))
      (node (ref "Q5") (pin "2") (pinfunction "S_2") (pintype "passive"))
      (node (ref "R40") (pin "2") (pinfunction "2_2") (pintype "passive"))
      (node (ref "U2") (pin "2") (pinfunction "VOUT_2") (pintype "output"))
    )
    (net (code "41") (name "/VCOM_DRIVER") (class "Default")
      (node (ref "R31") (pin "2") (pinfunction "2_2") (pintype "passive"))
      (node (ref "U7") (pin "30") (pinfunction "VCOM_DRIVER_30") (pintype "bidirectional"))
    )
    (net (code "42") (name "/WS_DO") (class "Default")
      (node (ref "U4") (pin "5") (pinfunction "A_5") (pintype "bidirectional"))
      (node (ref "U5") (pin "5") (pinfunction "SO_5") (pintype "output"))
    )
    (net (code "43") (name "/{slash}EPD_CS") (class "Default")
      (node (ref "R12") (pin "5") (pinfunction "2_5") (pintype "passive"))
      (node (ref "R20") (pin "8") (pinfunction "2_8") (pintype "passive"))
      (node (ref "U4") (pin "1") (pinfunction "~{OE}_1") (pintype "bidirectional"))
      (node (ref "U7") (pin "1") (pinfunction "/CS_1") (pintype "bidirectional"))
      (node (ref "U8") (pin "41") (pinfunction "/CS_41") (pintype "bidirectional"))
    )
    (net (code "44") (name "/{slash}SD_CS") (class "Default")
      (node (ref "J2") (pin "2") (pinfunction "CS_2") (pintype "bidirectional"))
      (node (ref "R11") (pin "2") (pinfunction "2_2") (pintype "passive"))
    )
    (net (code "45") (name "/{slash}WS_CS") (class "Default")
      (node (ref "D4") (pin "+") (pinfunction "+_+") (pintype "passive"))
      (node (ref "R13") (pin "1") (pinfunction "1_1") (pintype "passive"))
      (node (ref "U5") (pin "3") (pinfunction "CS#_3") (pintype "input"))
    )
    (net (code "46") (name "GND_POWER") (class "Default")
      (node (ref "C1") (pin "2") (pinfunction "2_2") (pintype "passive"))
      (node (ref "C16") (pin "1") (pinfunction "1_1") (pintype "passive"))
      (node (ref "C17") (pin "1") (pinfunction "1_1") (pintype "passive"))
      (node (ref "C18") (pin "1") (pinfunction "1_1") (pintype "passive"))
      (node (ref "C19") (pin "1") (pinfunction "1_1") (pintype "passive"))
      (node (ref "C2") (pin "2") (pinfunction "2_2") (pintype "passive"))
      (node (ref "C20") (pin "1") (pinfunction "1_1") (pintype "passive"))
      (node (ref "C21") (pin "1") (pinfunction "1_1") (pintype "passive"))
      (node (ref "C22") (pin "1") (pinfunction "1_1") (pintype "passive"))
      (node (ref "C23") (pin "1") (pinfunction "1_1") (pintype "passive"))
      (node (ref "C24") (pin "2") (pinfunction "2_2") (pintype "passive"))
      (node (ref "C25") (pin "2") (pinfunction "2_2") (pintype "passive"))
      (node (ref "C26") (pin "2") (pinfunction "2_2") (pintype "passive"))
      (node (ref "C27") (pin "2") (pinfunction "2_2") (pintype "passive"))
      (node (ref "C28") (pin "1") (pinfunction "1_1") (pintype "passive"))
      (node (ref "C29") (pin "-") (pinfunction "-_-") (pintype "passive"))
      (node (ref "C30") (pin "1") (pinfunction "1_1") (pintype "passive"))
      (node (ref "C40") (pin "1") (pinfunction "1_1") (pintype "passive"))
      (node (ref "C41") (pin "1") (pinfunction "1_1") (pintype "passive"))
      (node (ref "C42") (pin "1") (pinfunction "1_1") (pintype "passive"))
      (node (ref "C43") (pin "1") (pinfunction "1_1") (pintype "passive"))
      (node (ref "C44") (pin "1") (pinfunction "1_1") (pintype "passive"))
      (node (ref "C45") (pin "1") (pinfunction "1_1") (pintype "passive"))
      (node (ref "C46") (pin "1") (pinfunction "1_1") (pintype "passive"))
      (node (ref "C47") (pin "1") (pinfunction "1_1") (pintype "passive"))
      (node (ref "C48") (pin "1") (pinfunction "1_1") (pintype "passive"))
      (node (ref "C49") (pin "1") (pinfunction "1_1") (pintype "passive"))
      (node (ref "C50") (pin "1") (pinfunction "1_1") (pintype "passive"))
      (node (ref "C51") (pin "1") (pinfunction "1_1") (pintype "passive"))
      (node (ref "C52") (pin "1") (pinfunction "1_1") (pintype "passive"))
      (node (ref "C53") (pin "1") (pinfunction "1_1") (pintype "passive"))
      (node (ref "C54") (pin "2") (pinfunction "2_2") (pintype "passive"))
      (node (ref "C55") (pin "2") (pinfunction "2_2") (pintype "passive"))
      (node (ref "C56") (pin "1") (pinfunction "1_1") (pintype "passive"))
      (node (ref "C6") (pin "2") (pinfunction "2_2") (pintype "passive"))
      (node (ref "D6") (pin "-") (pinfunction "-_-") (pintype "passive"))
      (node (ref "GND") (pin "T") (pinfunction "T_T") (pintype "bidirectional"))
      (node (ref "J2") (pin "6") (pinfunction "VSS_6") (pintype "bidirectional"))
      (node (ref "J2") (pin "G1") (pinfunction "G1_G1") (pintype "bidirectional"))
      (node (ref "J2") (pin "G2") (pinfunction "G2_G2") (pintype "bidirectional"))
      (node (ref "J2") (pin "G3") (pinfunction "G3_G3") (pintype "bidirectional"))
      (node (ref "J2") (pin "G4") (pinfunction "G4_G4") (pintype "bidirectional"))
      (node (ref "J4") (pin "7") (pinfunction "7_7") (pintype "bidirectional"))
      (node (ref "J6") (pin "2") (pinfunction "2_2") (pintype "bidirectional"))
      (node (ref "J6") (pin "3") (pinfunction "3_3") (pintype "bidirectional"))
      (node (ref "J7") (pin "3") (pinfunction "3_3") (pintype "bidirectional"))
      (node (ref "Q2") (pin "2") (pinfunction "S_2") (pintype "passive"))
      (node (ref "R14") (pin "1") (pinfunction "1_1") (pintype "passive"))
      (node (ref "R18") (pin "1") (pinfunction "1_1") (pintype "passive"))
      (node (ref "R2") (pin "2") (pinfunction "2_2") (pintype "passive"))
      (node (ref "R21") (pin "1") (pinfunction "1_1") (pintype "passive"))
      (node (ref "R21") (pin "2") (pinfunction "1_2") (pintype "passive"))
      (node (ref "R21") (pin "3") (pinfunction "1_3") (pintype "passive"))
      (node (ref "R21") (pin "4") (pinfunction "1_4") (pintype "passive"))
      (node (ref "R23") (pin "1") (pinfunction "1_1") (pintype "passive"))
      (node (ref "R28") (pin "1") (pinfunction "1_1") (pintype "passive"))
      (node (ref "R3") (pin "2") (pinfunction "2_2") (pintype "passive"))
      (node (ref "R37") (pin "2") (pinfunction "2_2") (pintype "passive"))
      (node (ref "R39") (pin "1") (pinfunction "1_1") (pintype "passive"))
      (node (ref "SW1") (pin "1") (pinfunction "1_1") (pintype "bidirectional"))
      (node (ref "SW1") (pin "S1") (pinfunction "S1_S1") (pintype "bidirectional"))
      (node (ref "SW1") (pin "S2") (pinfunction "S2_S2") (pintype "bidirectional"))
      (node (ref "TP7") (pin "T") (pinfunction "T_T") (pintype "bidirectional"))
      (node (ref "TP8") (pin "T") (pinfunction "T_T") (pintype "bidirectional"))
      (node (ref "TP9") (pin "T") (pinfunction "T_T") (pintype "bidirectional"))
      (node (ref "U2") (pin "1") (pinfunction "VSS_1") (pintype "power_in"))
      (node (ref "U3") (pin "1") (pinfunction "~{OE}_1") (pintype "bidirectional"))
      (node (ref "U3") (pin "10") (pinfunction "~{OE}_10") (pintype "bidirectional"))
      (node (ref "U3") (pin "13") (pinfunction "~{OE}_13") (pintype "bidirectional"))
      (node (ref "U3") (pin "4") (pinfunction "~{OE}_4") (pintype "bidirectional"))
      (node (ref "U3") (pin "7") (pinfunction "GND_7") (pintype "power_in"))
      (node (ref "U4") (pin "13") (pinfunction "~{OE}_13") (pintype "bidirectional"))
      (node (ref "U4") (pin "7") (pinfunction "GND_7") (pintype "power_in"))
      (node (ref "U5") (pin "2") (pinfunction "GND_2") (pintype "power_in"))
      (node (ref "U6") (pin "1") (pinfunction "~{OE}_1") (pintype "bidirectional"))
      (node (ref "U6") (pin "10") (pinfunction "~{OE}_10") (pintype "bidirectional"))
      (node (ref "U6") (pin "13") (pinfunction "~{OE}_13") (pintype "bidirectional"))
      (node (ref "U6") (pin "4") (pinfunction "~{OE}_4") (pintype "bidirectional"))
      (node (ref "U6") (pin "7") (pinfunction "GND_7") (pintype "power_in"))
      (node (ref "U7") (pin "3") (pinfunction "ID_3") (pintype "bidirectional"))
      (node (ref "U7") (pin "33") (pinfunction "VSS_33") (pintype "bidirectional"))
      (node (ref "U7") (pin "P1") (pinfunction "P1_P1") (pintype "bidirectional"))
      (node (ref "U7") (pin "P2") (pinfunction "P2_P2") (pintype "bidirectional"))
      (node (ref "U8") (pin "36") (pinfunction "VSS_36") (pintype "bidirectional"))
      (node (ref "U8") (pin "40") (pinfunction "ID_40") (pintype "bidirectional"))
      (node (ref "U8") (pin "50") (pinfunction "VSS_50") (pintype "bidirectional"))
      (node (ref "U8") (pin "8") (pinfunction "VSS_8") (pintype "bidirectional"))
      (node (ref "U8") (pin "P1") (pinfunction "P1_P1") (pintype "bidirectional"))
      (node (ref "U8") (pin "P2") (pinfunction "P2_P2") (pintype "bidirectional"))
      (node (ref "U9") (pin "2") (pinfunction "VSS_2") (pintype "power_in"))
    )
    (net (code "47") (name "Net-(C15-Pad2)") (class "Default")
      (node (ref "C15") (pin "2") (pinfunction "2_2") (pintype "passive"))
      (node (ref "D5") (pin "-") (pinfunction "-_-") (pintype "passive"))
      (node (ref "D6") (pin "+") (pinfunction "+_+") (pintype "passive"))
    )
    (net (code "48") (name "Net-(PWR--)") (class "Default")
      (node (ref "PWR") (pin "2") (pinfunction "-_2") (pintype "passive"))
      (node (ref "R2") (pin "1") (pinfunction "1_1") (pintype "passive"))
    )
    (net (code "49") (name "Net-(Q2-D)") (class "Default")
      (node (ref "Q2") (pin "3") (pinfunction "D_3") (pintype "passive"))
      (node (ref "Q3") (pin "1") (pinfunction "G_1") (pintype "passive"))
      (node (ref "R25") (pin "2") (pinfunction "2_2") (pintype "passive"))
    )
    (net (code "50") (name "Net-(Q2-G)") (class "Default")
      (node (ref "Q2") (pin "1") (pinfunction "G_1") (pintype "passive"))
      (node (ref "R27") (pin "2") (pinfunction "2_2") (pintype "passive"))
      (node (ref "R28") (pin "2") (pinfunction "2_2") (pintype "passive"))
    )
    (net (code "51") (name "Net-(Q5-G)") (class "Default")
      (node (ref "Q5") (pin "1") (pinfunction "G_1") (pintype "passive"))
      (node (ref "R19") (pin "2") (pinfunction "2_2") (pintype "passive"))
    )
    (net (code "52") (name "Net-(Q7-D)") (class "Default")
      (node (ref "C15") (pin "1") (pinfunction "1_1") (pintype "passive"))
      (node (ref "Q7") (pin "3") (pinfunction "D_3") (pintype "passive"))
      (node (ref "R26") (pin "1") (pinfunction "1_1") (pintype "passive"))
    )
    (net (code "53") (name "Net-(Q7-S)") (class "Default")
      (node (ref "D7") (pin "-") (pinfunction "-_-") (pintype "passive"))
      (node (ref "Q7") (pin "2") (pinfunction "S_2") (pintype "passive"))
      (node (ref "R29") (pin "1") (pinfunction "1_1") (pintype "passive"))
      (node (ref "R30") (pin "1") (pinfunction "1_1") (pintype "passive"))
    )
    (net (code "54") (name "Net-(Q8-G)") (class "Default")
      (node (ref "Q8") (pin "1") (pinfunction "G_1") (pintype "passive"))
      (node (ref "Q9") (pin "1") (pinfunction "G_1") (pintype "passive"))
      (node (ref "R39") (pin "2") (pinfunction "2_2") (pintype "passive"))
      (node (ref "R42") (pin "1") (pinfunction "1_1") (pintype "passive"))
    )
    (net (code "55") (name "Net-(Q8-S)") (class "Default")
      (node (ref "Q8") (pin "2") (pinfunction "S_2") (pintype "passive"))
      (node (ref "Q9") (pin "2") (pinfunction "S_2") (pintype "passive"))
      (node (ref "R18") (pin "2") (pinfunction "2_2") (pintype "passive"))
    )
    (net (code "56") (name "Net-(Q10-D)") (class "Default")
      (node (ref "Q10") (pin "3") (pinfunction "D_3") (pintype "passive"))
      (node (ref "R16") (pin "1") (pinfunction "1_1") (pintype "passive"))
    )
    (net (code "57") (name "Net-(Q10-G)") (class "Default")
      (node (ref "Q10") (pin "1") (pinfunction "G_1") (pintype "passive"))
      (node (ref "R36") (pin "2") (pinfunction "2_2") (pintype "passive"))
    )
    (net (code "58") (name "Net-(Q11-G)") (class "Default")
      (node (ref "Q11") (pin "1") (pinfunction "G_1") (pintype "passive"))
      (node (ref "R16") (pin "2") (pinfunction "1_2") (pintype "passive"))
      (node (ref "R16") (pin "8") (pinfunction "2_8") (pintype "passive"))
    )
    (net (code "59") (name "Net-(R1-Pad2)") (class "Default")
      (node (ref "R1") (pin "2") (pinfunction "2_2") (pintype "passive"))
      (node (ref "R6") (pin "1") (pinfunction "1_1") (pintype "passive"))
    )
    (net (code "60") (name "Net-(R12B-1)") (class "Default")
      (node (ref "R12") (pin "2") (pinfunction "1_2") (pintype "passive"))
      (node (ref "U4") (pin "6") (pinfunction "Y_6") (pintype "bidirectional"))
    )
    (net (code "61") (name "Net-(R12C-1)") (class "Default")
      (node (ref "R12") (pin "3") (pinfunction "1_3") (pintype "passive"))
      (node (ref "U4") (pin "8") (pinfunction "Y_8") (pintype "bidirectional"))
    )
    (net (code "62") (name "Net-(R12D-1)") (class "Default")
      (node (ref "R12") (pin "4") (pinfunction "1_4") (pintype "passive"))
      (node (ref "U4") (pin "11") (pinfunction "Y_11") (pintype "bidirectional"))
    )
    (net (code "63") (name "Net-(R15B-1)") (class "Default")
      (node (ref "R15") (pin "2") (pinfunction "1_2") (pintype "passive"))
      (node (ref "U6") (pin "6") (pinfunction "Y_6") (pintype "bidirectional"))
    )
    (net (code "64") (name "Net-(R15C-1)") (class "Default")
      (node (ref "R15") (pin "3") (pinfunction "1_3") (pintype "passive"))
      (node (ref "U6") (pin "8") (pinfunction "Y_8") (pintype "bidirectional"))
    )
    (net (code "65") (name "Net-(R15D-1)") (class "Default")
      (node (ref "R15") (pin "4") (pinfunction "1_4") (pintype "passive"))
      (node (ref "U6") (pin "11") (pinfunction "Y_11") (pintype "bidirectional"))
    )
    (net (code "66") (name "Net-(R20B-1)") (class "Default")
      (node (ref "R20") (pin "1") (pinfunction "1_1") (pintype "passive"))
      (node (ref "R20") (pin "2") (pinfunction "1_2") (pintype "passive"))
      (node (ref "R20") (pin "3") (pinfunction "1_3") (pintype "passive"))
      (node (ref "R24") (pin "2") (pinfunction "2_2") (pintype "passive"))
    )
    (net (code "67") (name "Net-(R31-Pad1)") (class "Default")
      (node (ref "R31") (pin "1") (pinfunction "1_1") (pintype "passive"))
      (node (ref "R32") (pin "2") (pinfunction "2_2") (pintype "passive"))
    )
    (net (code "68") (name "Net-(RST-+)") (class "Default")
      (node (ref "R5") (pin "2") (pinfunction "2_2") (pintype "passive"))
      (node (ref "RST") (pin "1") (pinfunction "+_1") (pintype "passive"))
    )
    (net (code "69") (name "Net-(U2-VIN)") (class "Default")
      (node (ref "C30") (pin "2") (pinfunction "2_2") (pintype "passive"))
      (node (ref "D3") (pin "-") (pinfunction "-_-") (pintype "passive"))
      (node (ref "U2") (pin "3") (pinfunction "VIN_3") (pintype "input"))
    )
    (net (code "70") (name "Net-(U3A-Y)") (class "Default")
      (node (ref "R8") (pin "1") (pinfunction "1_1") (pintype "passive"))
      (node (ref "U3") (pin "3") (pinfunction "Y_3") (pintype "bidirectional"))
    )
    (net (code "71") (name "Net-(U3B-Y)") (class "Default")
      (node (ref "R10") (pin "1") (pinfunction "1_1") (pintype "passive"))
      (node (ref "U3") (pin "6") (pinfunction "Y_6") (pintype "bidirectional"))
    )
    (net (code "72") (name "Net-(U3C-Y)") (class "Default")
      (node (ref "R9") (pin "1") (pinfunction "1_1") (pintype "passive"))
      (node (ref "U3") (pin "8") (pinfunction "Y_8") (pintype "bidirectional"))
    )
    (net (code "73") (name "Net-(U3D-Y)") (class "Default")
      (node (ref "R11") (pin "1") (pinfunction "1_1") (pintype "passive"))
      (node (ref "U3") (pin "11") (pinfunction "Y_11") (pintype "bidirectional"))
    )
    (net (code "74") (name "Net-(U4A-Y)") (class "Default")
      (node (ref "R12") (pin "1") (pinfunction "1_1") (pintype "passive"))
      (node (ref "U4") (pin "3") (pinfunction "Y_3") (pintype "bidirectional"))
    )
    (net (code "75") (name "Net-(U6A-Y)") (class "Default")
      (node (ref "R15") (pin "1") (pinfunction "1_1") (pintype "passive"))
      (node (ref "U6") (pin "3") (pinfunction "Y_3") (pintype "bidirectional"))
    )
    (net (code "76") (name "Net-(U7-C11M)") (class "Default")
      (node (ref "C14") (pin "1") (pinfunction "1_1") (pintype "passive"))
      (node (ref "U7") (pin "28") (pinfunction "C11M_28") (pintype "bidirectional"))
    )
    (net (code "77") (name "Net-(U7-C11P)") (class "Default")
      (node (ref "C14") (pin "2") (pinfunction "2_2") (pintype "passive"))
      (node (ref "U7") (pin "29") (pinfunction "C11P_29") (pintype "bidirectional"))
    )
    (net (code "78") (name "Net-(U7-C12M)") (class "Default")
      (node (ref "C13") (pin "1") (pinfunction "1_1") (pintype "passive"))
      (node (ref "U7") (pin "26") (pinfunction "C12M_26") (pintype "bidirectional"))
    )
    (net (code "79") (name "Net-(U7-C12P)") (class "Default")
      (node (ref "C13") (pin "2") (pinfunction "2_2") (pintype "passive"))
      (node (ref "U7") (pin "27") (pinfunction "C12P_27") (pintype "bidirectional"))
    )
    (net (code "80") (name "Net-(U7-C13M)") (class "Default")
      (node (ref "C12") (pin "1") (pinfunction "1_1") (pintype "passive"))
      (node (ref "U7") (pin "24") (pinfunction "C13M_24") (pintype "bidirectional"))
    )
    (net (code "81") (name "Net-(U7-C13P)") (class "Default")
      (node (ref "C12") (pin "2") (pinfunction "2_2") (pintype "passive"))
      (node (ref "U7") (pin "25") (pinfunction "C13P_25") (pintype "bidirectional"))
    )
    (net (code "82") (name "Net-(U7-C14M)") (class "Default")
      (node (ref "C11") (pin "1") (pinfunction "1_1") (pintype "passive"))
      (node (ref "U7") (pin "22") (pinfunction "C14M_22") (pintype "bidirectional"))
    )
    (net (code "83") (name "Net-(U7-C14P)") (class "Default")
      (node (ref "C11") (pin "2") (pinfunction "2_2") (pintype "passive"))
      (node (ref "U7") (pin "23") (pinfunction "C14P_23") (pintype "bidirectional"))
    )
    (net (code "84") (name "Net-(U7-C15M)") (class "Default")
      (node (ref "C10") (pin "1") (pinfunction "1_1") (pintype "passive"))
      (node (ref "U7") (pin "20") (pinfunction "C15M_20") (pintype "bidirectional"))
    )
    (net (code "85") (name "Net-(U7-C15P)") (class "Default")
      (node (ref "C10") (pin "2") (pinfunction "2_2") (pintype "passive"))
      (node (ref "U7") (pin "21") (pinfunction "C15P_21") (pintype "bidirectional"))
    )
    (net (code "86") (name "Net-(U7-C16M)") (class "Default")
      (node (ref "C37") (pin "1") (pinfunction "1_1") (pintype "passive"))
      (node (ref "U7") (pin "18") (pinfunction "C16M_18") (pintype "bidirectional"))
    )
    (net (code "87") (name "Net-(U7-C16P)") (class "Default")
      (node (ref "C37") (pin "2") (pinfunction "2_2") (pintype "passive"))
      (node (ref "U7") (pin "19") (pinfunction "C16P_19") (pintype "bidirectional"))
    )
    (net (code "88") (name "Net-(U7-C21M)") (class "Default")
      (node (ref "C32") (pin "1") (pinfunction "1_1") (pintype "passive"))
      (node (ref "U7") (pin "16") (pinfunction "C21M_16") (pintype "bidirectional"))
    )
    (net (code "89") (name "Net-(U7-C21P)") (class "Default")
      (node (ref "C32") (pin "2") (pinfunction "2_2") (pintype "passive"))
      (node (ref "U7") (pin "17") (pinfunction "C21P_17") (pintype "bidirectional"))
    )
    (net (code "90") (name "Net-(U7-C31M)") (class "Default")
      (node (ref "C35") (pin "1") (pinfunction "1_1") (pintype "passive"))
      (node (ref "U7") (pin "14") (pinfunction "C31M_14") (pintype "bidirectional"))
    )
    (net (code "91") (name "Net-(U7-C31P)") (class "Default")
      (node (ref "C35") (pin "2") (pinfunction "2_2") (pintype "passive"))
      (node (ref "U7") (pin "15") (pinfunction "C31P_15") (pintype "bidirectional"))
    )
    (net (code "92") (name "Net-(U7-C41M)") (class "Default")
      (node (ref "C39") (pin "2") (pinfunction "2_2") (pintype "passive"))
      (node (ref "U7") (pin "13") (pinfunction "C41M_13") (pintype "bidirectional"))
    )
    (net (code "93") (name "Net-(U7-C41P)") (class "Default")
      (node (ref "C39") (pin "1") (pinfunction "1_1") (pintype "passive"))
      (node (ref "U7") (pin "12") (pinfunction "C41P_12") (pintype "bidirectional"))
    )
    (net (code "94") (name "Net-(U7-C42M)") (class "Default")
      (node (ref "C34") (pin "2") (pinfunction "2_2") (pintype "passive"))
      (node (ref "U7") (pin "11") (pinfunction "C42M_11") (pintype "bidirectional"))
    )
    (net (code "95") (name "Net-(U7-C42P)") (class "Default")
      (node (ref "C34") (pin "1") (pinfunction "1_1") (pintype "passive"))
      (node (ref "U7") (pin "10") (pinfunction "C42P_10") (pintype "bidirectional"))
    )
    (net (code "96") (name "Net-(U8-C11M)") (class "Default")
      (node (ref "C3") (pin "2") (pinfunction "2_2") (pintype "passive"))
      (node (ref "U8") (pin "13") (pinfunction "C11M_13") (pintype "bidirectional"))
    )
    (net (code "97") (name "Net-(U8-C11P)") (class "Default")
      (node (ref "C3") (pin "1") (pinfunction "1_1") (pintype "passive"))
      (node (ref "U8") (pin "12") (pinfunction "C11P_12") (pintype "bidirectional"))
    )
    (net (code "98") (name "Net-(U8-C12M)") (class "Default")
      (node (ref "C4") (pin "2") (pinfunction "2_2") (pintype "passive"))
      (node (ref "U8") (pin "15") (pinfunction "C12M_15") (pintype "bidirectional"))
    )
    (net (code "99") (name "Net-(U8-C12P)") (class "Default")
      (node (ref "C4") (pin "1") (pinfunction "1_1") (pintype "passive"))
      (node (ref "U8") (pin "14") (pinfunction "C12P_14") (pintype "bidirectional"))
    )
    (net (code "100") (name "Net-(U8-C13M)") (class "Default")
      (node (ref "C31") (pin "2") (pinfunction "2_2") (pintype "passive"))
      (node (ref "U8") (pin "17") (pinfunction "C13M_17") (pintype "bidirectional"))
    )
    (net (code "101") (name "Net-(U8-C13P)") (class "Default")
      (node (ref "C31") (pin "1") (pinfunction "1_1") (pintype "passive"))
      (node (ref "U8") (pin "16") (pinfunction "C13P_16") (pintype "bidirectional"))
    )
    (net (code "102") (name "Net-(U8-C14M)") (class "Default")
      (node (ref "C8") (pin "2") (pinfunction "2_2") (pintype "passive"))
      (node (ref "U8") (pin "19") (pinfunction "C14M_19") (pintype "bidirectional"))
    )
    (net (code "103") (name "Net-(U8-C14P)") (class "Default")
      (node (ref "C8") (pin "1") (pinfunction "1_1") (pintype "passive"))
      (node (ref "U8") (pin "18") (pinfunction "C14P_18") (pintype "bidirectional"))
    )
    (net (code "104") (name "Net-(U8-C15M)") (class "Default")
      (node (ref "C33") (pin "2") (pinfunction "2_2") (pintype "passive"))
      (node (ref "U8") (pin "21") (pinfunction "C15M_21") (pintype "bidirectional"))
    )
    (net (code "105") (name "Net-(U8-C15P)") (class "Default")
      (node (ref "C33") (pin "1") (pinfunction "1_1") (pintype "passive"))
      (node (ref "U8") (pin "20") (pinfunction "C15P_20") (pintype "bidirectional"))
    )
    (net (code "106") (name "Net-(U8-C16M)") (class "Default")
      (node (ref "C5") (pin "2") (pinfunction "2_2") (pintype "passive"))
      (node (ref "U8") (pin "23") (pinfunction "C16M_23") (pintype "bidirectional"))
    )
    (net (code "107") (name "Net-(U8-C16P)") (class "Default")
      (node (ref "C5") (pin "1") (pinfunction "1_1") (pintype "passive"))
      (node (ref "U8") (pin "22") (pinfunction "C16P_22") (pintype "bidirectional"))
    )
    (net (code "108") (name "Net-(U8-C21M)") (class "Default")
      (node (ref "C7") (pin "2") (pinfunction "2_2") (pintype "passive"))
      (node (ref "U8") (pin "25") (pinfunction "C21M_25") (pintype "bidirectional"))
    )
    (net (code "109") (name "Net-(U8-C21P)") (class "Default")
      (node (ref "C7") (pin "1") (pinfunction "1_1") (pintype "passive"))
      (node (ref "U8") (pin "24") (pinfunction "C21P_24") (pintype "bidirectional"))
    )
    (net (code "110") (name "Net-(U8-C31M)") (class "Default")
      (node (ref "C36") (pin "2") (pinfunction "2_2") (pintype "passive"))
      (node (ref "U8") (pin "27") (pinfunction "C31M_27") (pintype "bidirectional"))
    )
    (net (code "111") (name "Net-(U8-C31P)") (class "Default")
      (node (ref "C36") (pin "1") (pinfunction "1_1") (pintype "passive"))
      (node (ref "U8") (pin "26") (pinfunction "C31P_26") (pintype "bidirectional"))
    )
    (net (code "112") (name "Net-(U8-C41M)") (class "Default")
      (node (ref "C9") (pin "1") (pinfunction "1_1") (pintype "passive"))
      (node (ref "U8") (pin "28") (pinfunction "C41M_28") (pintype "bidirectional"))
    )
    (net (code "113") (name "Net-(U8-C41P)") (class "Default")
      (node (ref "C9") (pin "2") (pinfunction "2_2") (pintype "passive"))
      (node (ref "U8") (pin "29") (pinfunction "C41P_29") (pintype "bidirectional"))
    )
    (net (code "114") (name "Net-(U8-C42M)") (class "Default")
      (node (ref "C38") (pin "1") (pinfunction "1_1") (pintype "passive"))
      (node (ref "U8") (pin "30") (pinfunction "C42M_30") (pintype "bidirectional"))
    )
    (net (code "115") (name "Net-(U8-C42P)") (class "Default")
      (node (ref "C38") (pin "2") (pinfunction "2_2") (pintype "passive"))
      (node (ref "U8") (pin "31") (pinfunction "C42P_31") (pintype "bidirectional"))
    )
    (net (code "116") (name "Net-(U8-U_D)") (class "Default")
      (node (ref "R17") (pin "1") (pinfunction "1_1") (pintype "passive"))
      (node (ref "U8") (pin "43") (pinfunction "U_D_43") (pintype "bidirectional"))
    )
    (net (code "117") (name "Net-(U8-VCL)") (class "Default")
      (node (ref "C6") (pin "1") (pinfunction "1_1") (pintype "passive"))
      (node (ref "U8") (pin "32") (pinfunction "VCL_32") (pintype "bidirectional"))
    )
    (net (code "118") (name "Net-(U8-VCOM-DRIVER)") (class "Default")
      (node (ref "R1") (pin "1") (pinfunction "1_1") (pintype "passive"))
      (node (ref "U8") (pin "11") (pinfunction "VCOM-DRIVER_11") (pintype "bidirectional"))
    )
    (net (code "119") (name "Net-(U9-VDD)") (class "Default")
      (node (ref "C55") (pin "1") (pinfunction "1_1") (pintype "passive"))
      (node (ref "R22") (pin "2") (pinfunction "2_2") (pintype "passive"))
      (node (ref "U9") (pin "1") (pinfunction "VDD_1") (pintype "power_in"))
    )
    (net (code "120") (name "unconnected-(J2-CDN-Pad9)") (class "Default")
      (node (ref "J2") (pin "9") (pinfunction "CDN_9") (pintype "bidirectional"))
    )
    (net (code "121") (name "unconnected-(J2-DATA1-Pad8)") (class "Default")
      (node (ref "J2") (pin "8") (pinfunction "DATA1_8") (pintype "bidirectional"))
    )
    (net (code "122") (name "unconnected-(J2-DATA2-Pad1)") (class "Default")
      (node (ref "J2") (pin "1") (pinfunction "DATA2_1") (pintype "bidirectional"))
    )
    (net (code "123") (name "unconnected-(J3-Pad1)") (class "Default")
      (node (ref "J3") (pin "1") (pinfunction "1_1") (pintype "bidirectional"))
    )
    (net (code "124") (name "unconnected-(J3-Pad2)") (class "Default")
      (node (ref "J3") (pin "2") (pinfunction "2_2") (pintype "bidirectional"))
    )
    (net (code "125") (name "unconnected-(J4-Pad4)") (class "Default")
      (node (ref "J4") (pin "4") (pinfunction "4_4") (pintype "bidirectional"))
    )
    (net (code "126") (name "unconnected-(J4-Pad5)") (class "Default")
      (node (ref "J4") (pin "5") (pinfunction "5_5") (pintype "bidirectional"))
    )
    (net (code "127") (name "unconnected-(J4-Pad6)") (class "Default")
      (node (ref "J4") (pin "6") (pinfunction "6_6") (pintype "bidirectional"))
    )
    (net (code "128") (name "unconnected-(J4-Pad8)") (class "Default")
      (node (ref "J4") (pin "8") (pinfunction "8_8") (pintype "bidirectional"))
    )
    (net (code "129") (name "unconnected-(J5-Pad5)") (class "Default")
      (node (ref "J5") (pin "5") (pinfunction "5_5") (pintype "bidirectional"))
    )
    (net (code "130") (name "unconnected-(J5-Pad6)") (class "Default")
      (node (ref "J5") (pin "6") (pinfunction "6_6") (pintype "bidirectional"))
    )
    (net (code "131") (name "unconnected-(J6-Pad1)") (class "Default")
      (node (ref "J6") (pin "1") (pinfunction "1_1") (pintype "bidirectional"))
    )
    (net (code "132") (name "unconnected-(J7-Pad1)") (class "Default")
      (node (ref "J7") (pin "1") (pinfunction "1_1") (pintype "bidirectional"))
    )
    (net (code "133") (name "unconnected-(J7-Pad4)") (class "Default")
      (node (ref "J7") (pin "4") (pinfunction "4_4") (pintype "bidirectional"))
    )
    (net (code "134") (name "unconnected-(R16D-1-Pad4)") (class "Default")
      (node (ref "R16") (pin "4") (pinfunction "1_4") (pintype "passive"))
    )
    (net (code "135") (name "unconnected-(R16D-2-Pad5)") (class "Default")
      (node (ref "R16") (pin "5") (pinfunction "2_5") (pintype "passive"))
    )
    (net (code "136") (name "unconnected-(R20D-1-Pad4)") (class "Default")
      (node (ref "R20") (pin "4") (pinfunction "1_4") (pintype "passive"))
    )
    (net (code "137") (name "unconnected-(R20D-2-Pad5)") (class "Default")
      (node (ref "R20") (pin "5") (pinfunction "2_5") (pintype "passive"))
    )
    (net (code "138") (name "unconnected-(U8-IF0-Pad33)") (class "Default")
      (node (ref "U8") (pin "33") (pinfunction "IF0_33") (pintype "bidirectional"))
    )
    (net (code "139") (name "unconnected-(U8-IF1-Pad34)") (class "Default")
      (node (ref "U8") (pin "34") (pinfunction "IF1_34") (pintype "bidirectional"))
    )
    (net (code "140") (name "unconnected-(U8-STV_OUT-Pad46)") (class "Default")
      (node (ref "U8") (pin "46") (pinfunction "STV_OUT_46") (pintype "bidirectional"))
    )
  )
)
